# MT3608_2A.net
KiCad netlist of a schematic drawn in Altium Designer
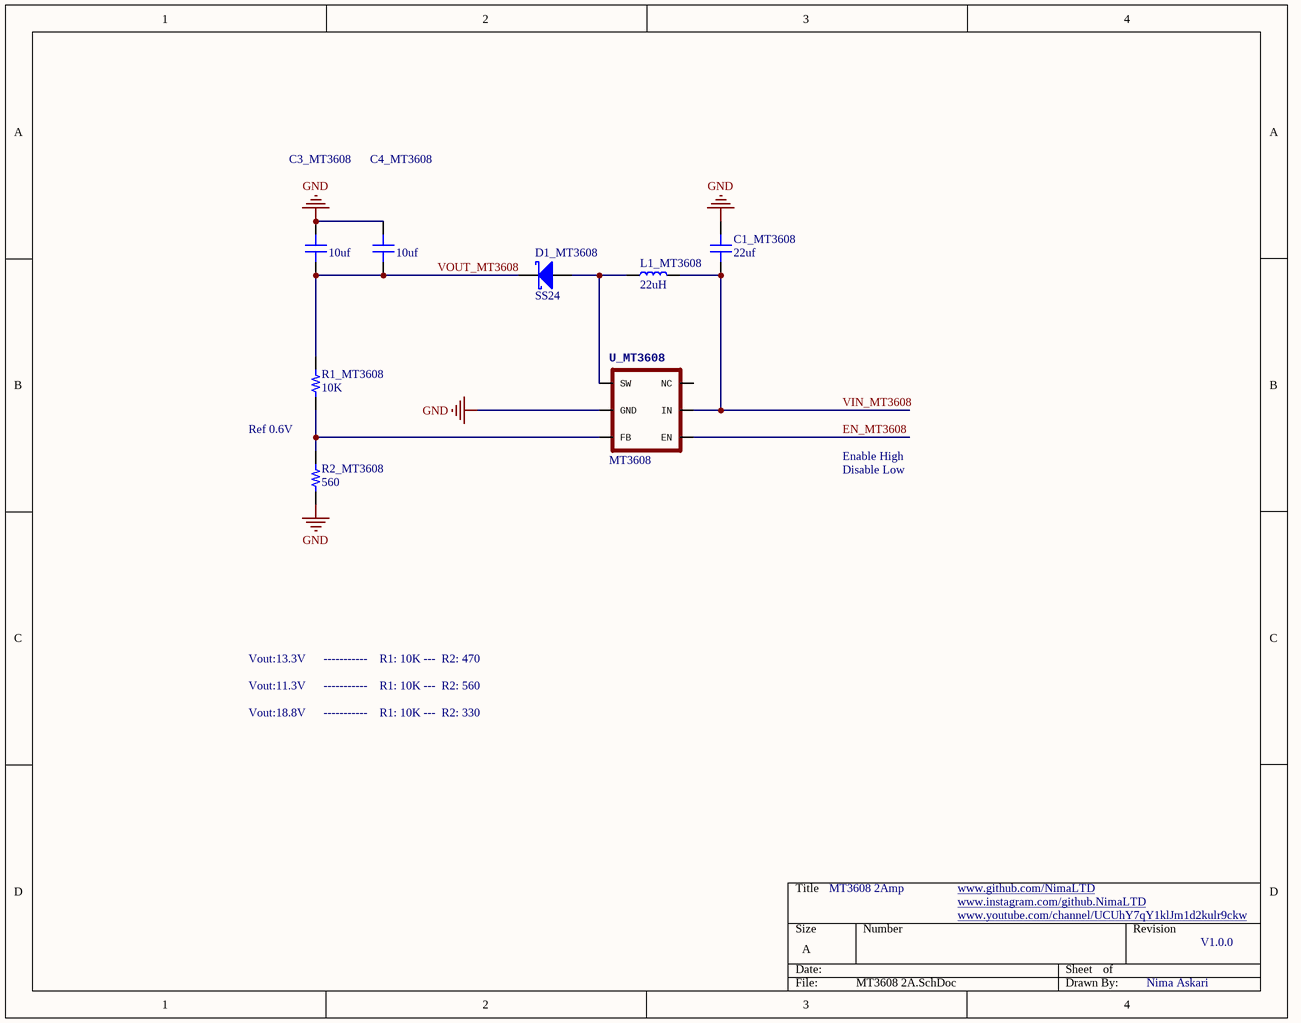
[diagram p0: MT3608 2A.SchDoc]

(export (version "E")
  (design (tool "Eeschema 10.0.6"))
  (components
    (comp (ref "C1_MT3608")
      (value "22uf")
      (footprint "CAP 1206")
      (description "SMT Capacitor")
      (libsource (lib "CAPACITOR") (part "Cap SMD 1206"))
    )
    (comp (ref "C3_MT3608")
      (value "10uf")
      (footprint "CAP 1206")
      (description "SMT Capacitor")
      (libsource (lib "CAPACITOR") (part "Cap SMD 1206"))
    )
    (comp (ref "C4_MT3608")
      (value "10uf")
      (footprint "CAP 1206")
      (description "SMT Capacitor")
      (libsource (lib "CAPACITOR") (part "Cap SMD 1206"))
    )
    (comp (ref "D1_MT3608")
      (value "SS24 SMD")
      (footprint "DO214AA SMB")
      (description "2A Schottky")
      (fields (field (name "PARAMETER 1") "SS24"))
      (libsource (lib "DIODE") (part "SS24 SMD"))
    )
    (comp (ref "L1_MT3608")
      (value "22uH")
      (footprint "IND 10X11")
      (description "SMT Inductor")
      (fields (field (name "Comment") "Inductor SMD POWER 10X11mm"))
      (libsource (lib "INDUCTOR") (part "Inductor SMD POWER 10X11mm"))
    )
    (comp (ref "R1_MT3608")
      (value "10K")
      (footprint "RES 0805")
      (description "SMD Resistor")
      (libsource (lib "RESISTOR") (part "Res SMD 0805"))
    )
    (comp (ref "R2_MT3608")
      (value "560")
      (footprint "RES 0805")
      (description "SMD Resistor")
      (libsource (lib "RESISTOR") (part "Res SMD 0805"))
    )
    (comp (ref "U_MT3608")
      (value "MT3608")
      (footprint "SOT23-6")
      (description "Boost")
      (fields (field (name "PARAMETER") "MT3608"))
      (libsource (lib "IC") (part "MT3608"))
    )
  )
  (nets
    (net (code "1") (name "/EN_MT3608") (class "Default")
      (node (ref "U_MT3608") (pin "4") (pinfunction "EN_4") (pintype "passive"))
    )
    (net (code "2") (name "/VIN_MT3608") (class "Default")
      (node (ref "C1_MT3608") (pin "1") (pinfunction "1_1") (pintype "passive"))
      (node (ref "L1_MT3608") (pin "2") (pinfunction "2_2") (pintype "passive"))
      (node (ref "U_MT3608") (pin "5") (pinfunction "IN_5") (pintype "passive"))
    )
    (net (code "3") (name "/VOUT_MT3608") (class "Default")
      (node (ref "C3_MT3608") (pin "1") (pinfunction "1_1") (pintype "passive"))
      (node (ref "C4_MT3608") (pin "1") (pinfunction "1_1") (pintype "passive"))
      (node (ref "D1_MT3608") (pin "2") (pinfunction "K_2") (pintype "passive"))
      (node (ref "R1_MT3608") (pin "2") (pinfunction "2_2") (pintype "passive"))
    )
    (net (code "4") (name "GND") (class "Default")
      (node (ref "C1_MT3608") (pin "2") (pinfunction "2_2") (pintype "passive"))
      (node (ref "C3_MT3608") (pin "2") (pinfunction "2_2") (pintype "passive"))
      (node (ref "C4_MT3608") (pin "2") (pinfunction "2_2") (pintype "passive"))
      (node (ref "R2_MT3608") (pin "1") (pinfunction "1_1") (pintype "passive"))
      (node (ref "U_MT3608") (pin "2") (pinfunction "GND_2") (pintype "passive"))
    )
    (net (code "5") (name "Net-(D1_MT3608-A)") (class "Default")
      (node (ref "D1_MT3608") (pin "1") (pinfunction "A_1") (pintype "passive"))
      (node (ref "L1_MT3608") (pin "1") (pinfunction "1_1") (pintype "passive"))
      (node (ref "U_MT3608") (pin "1") (pinfunction "SW_1") (pintype "passive"))
    )
    (net (code "6") (name "Net-(U_MT3608-FB)") (class "Default")
      (node (ref "R1_MT3608") (pin "1") (pinfunction "1_1") (pintype "passive"))
      (node (ref "R2_MT3608") (pin "2") (pinfunction "2_2") (pintype "passive"))
      (node (ref "U_MT3608") (pin "3") (pinfunction "FB_3") (pintype "passive"))
    )
    (net (code "7") (name "unconnected-(U_MT3608-NC-Pad6)") (class "Default")
      (node (ref "U_MT3608") (pin "6") (pinfunction "NC_6") (pintype "passive"))
    )
  )
)
